# DrivenOutputs.net
KiCad netlist of a schematic drawn in Altium Designer
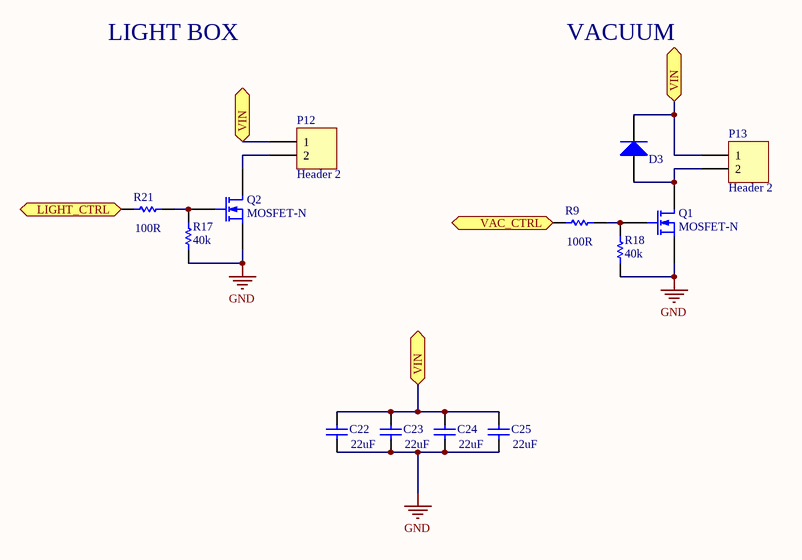
[diagram p0: DrivenOutputs.SchDoc]

(export (version "E")
  (design (tool "Eeschema 10.0.6"))
  (components
    (comp (ref "C22")
      (value "22uF")
      (footprint "0805")
      (description "Capacitor")
      (fields (field (name "Comment") "Cap") (field (name "PUBLISHER") "Altium Limited"))
      (libsource (lib "Miscellaneous Devices") (part "Cap"))
    )
    (comp (ref "C23")
      (value "22uF")
      (footprint "0805")
      (description "Capacitor")
      (fields (field (name "Comment") "Cap") (field (name "PUBLISHER") "Altium Limited"))
      (libsource (lib "Miscellaneous Devices") (part "Cap"))
    )
    (comp (ref "C24")
      (value "22uF")
      (footprint "0805")
      (description "Capacitor")
      (fields (field (name "Comment") "Cap") (field (name "PUBLISHER") "Altium Limited"))
      (libsource (lib "Miscellaneous Devices") (part "Cap"))
    )
    (comp (ref "C25")
      (value "22uF")
      (footprint "0805")
      (description "Capacitor")
      (fields (field (name "Comment") "Cap") (field (name "PUBLISHER") "Altium Limited"))
      (libsource (lib "Miscellaneous Devices") (part "Cap"))
    )
    (comp (ref "D3")
      (value "Diode MMBD914")
      (footprint "SOT-23")
      (description "Standard Diode")
      (fields
        (field (name "DIGI-KEY PART NO.") "MMBD914LT1GOSCT-ND")
        (field (name "MANUFACTURER PART NO.") "MMBD914LT1G")
      )
      (libsource (lib "Semiconductors") (part "Diode MMBD914"))
    )
    (comp (ref "P12")
      (value "Header 2")
      (footprint "HDR1X2")
      (description "Header, 2-Pin")
      (fields (field (name "PUBLISHER") "Altium Limited"))
      (libsource (lib "Miscellaneous Connectors") (part "Header 2"))
    )
    (comp (ref "P13")
      (value "Header 2")
      (footprint "HDR1X2")
      (description "Header, 2-Pin")
      (fields (field (name "PUBLISHER") "Altium Limited"))
      (libsource (lib "Miscellaneous Connectors") (part "Header 2"))
    )
    (comp (ref "Q1")
      (value "MOSFET-N")
      (footprint "DPAK")
      (description "N-Channel MOSFET")
      (fields
        (field (name "DIGI-KEY PART NO.") "497-2477-1-ND")
        (field (name "MANUFACTURER PART NO.") "STD5NK40ZT4")
      )
      (libsource (lib "Semiconductors") (part "N-Channel MOSFET"))
    )
    (comp (ref "Q2")
      (value "MOSFET-N")
      (footprint "DPAK")
      (description "N-Channel MOSFET")
      (fields
        (field (name "DIGI-KEY PART NO.") "497-2477-1-ND")
        (field (name "MANUFACTURER PART NO.") "STD5NK40ZT4")
      )
      (libsource (lib "Semiconductors") (part "N-Channel MOSFET"))
    )
    (comp (ref "R9")
      (value "100R")
      (footprint "0805")
      (description "Resistor")
      (fields (field (name "Comment") "Res1") (field (name "PUBLISHER") "Altium Limited"))
      (libsource (lib "Miscellaneous Devices") (part "Res1"))
    )
    (comp (ref "R17")
      (value "40k")
      (footprint "0805")
      (description "Chip Resistor")
      (fields (field (name "Comment") "Resistor"))
      (libsource (lib "RCL") (part "Resistor"))
    )
    (comp (ref "R18")
      (value "40k")
      (footprint "0805")
      (description "Chip Resistor")
      (fields (field (name "Comment") "Resistor"))
      (libsource (lib "RCL") (part "Resistor"))
    )
    (comp (ref "R21")
      (value "100R")
      (footprint "0805")
      (description "Resistor")
      (fields (field (name "Comment") "Res1") (field (name "PUBLISHER") "Altium Limited"))
      (libsource (lib "Miscellaneous Devices") (part "Res1"))
    )
  )
  (nets
    (net (code "1") (name "/LIGHT_CTRL") (class "Default")
      (node (ref "R21") (pin "1") (pinfunction "1_1") (pintype "passive"))
    )
    (net (code "2") (name "/VAC_CTRL") (class "Default")
      (node (ref "R9") (pin "1") (pinfunction "1_1") (pintype "passive"))
    )
    (net (code "3") (name "/VIN") (class "Default")
      (node (ref "C22") (pin "2") (pinfunction "2_2") (pintype "passive"))
      (node (ref "C23") (pin "2") (pinfunction "2_2") (pintype "passive"))
      (node (ref "C24") (pin "2") (pinfunction "2_2") (pintype "passive"))
      (node (ref "C25") (pin "2") (pinfunction "2_2") (pintype "passive"))
      (node (ref "D3") (pin "3") (pinfunction "K_3") (pintype "passive"))
      (node (ref "P12") (pin "1") (pinfunction "1_1") (pintype "passive"))
      (node (ref "P13") (pin "1") (pinfunction "1_1") (pintype "passive"))
    )
    (net (code "4") (name "GND") (class "Default")
      (node (ref "C22") (pin "1") (pinfunction "1_1") (pintype "passive"))
      (node (ref "C23") (pin "1") (pinfunction "1_1") (pintype "passive"))
      (node (ref "C24") (pin "1") (pinfunction "1_1") (pintype "passive"))
      (node (ref "C25") (pin "1") (pinfunction "1_1") (pintype "passive"))
      (node (ref "Q1") (pin "3") (pinfunction "S_3") (pintype "passive"))
      (node (ref "Q2") (pin "3") (pinfunction "S_3") (pintype "passive"))
      (node (ref "R17") (pin "1") (pinfunction "1_1") (pintype "passive"))
      (node (ref "R18") (pin "1") (pinfunction "1_1") (pintype "passive"))
    )
    (net (code "5") (name "Net-(D3-A)") (class "Default")
      (node (ref "D3") (pin "1") (pinfunction "A_1") (pintype "passive"))
      (node (ref "P13") (pin "2") (pinfunction "2_2") (pintype "passive"))
      (node (ref "Q1") (pin "2") (pinfunction "D_2") (pintype "passive"))
    )
    (net (code "6") (name "Net-(Q1-G)") (class "Default")
      (node (ref "Q1") (pin "1") (pinfunction "G_1") (pintype "passive"))
      (node (ref "R18") (pin "2") (pinfunction "2_2") (pintype "passive"))
      (node (ref "R9") (pin "2") (pinfunction "2_2") (pintype "passive"))
    )
    (net (code "7") (name "Net-(Q2-D)") (class "Default")
      (node (ref "P12") (pin "2") (pinfunction "2_2") (pintype "passive"))
      (node (ref "Q2") (pin "2") (pinfunction "D_2") (pintype "passive"))
    )
    (net (code "8") (name "Net-(Q2-G)") (class "Default")
      (node (ref "Q2") (pin "1") (pinfunction "G_1") (pintype "passive"))
      (node (ref "R17") (pin "2") (pinfunction "2_2") (pintype "passive"))
      (node (ref "R21") (pin "2") (pinfunction "2_2") (pintype "passive"))
    )
  )
)
